# KeyTop.net
KiCad netlist of a schematic drawn in EasyEDA Pro
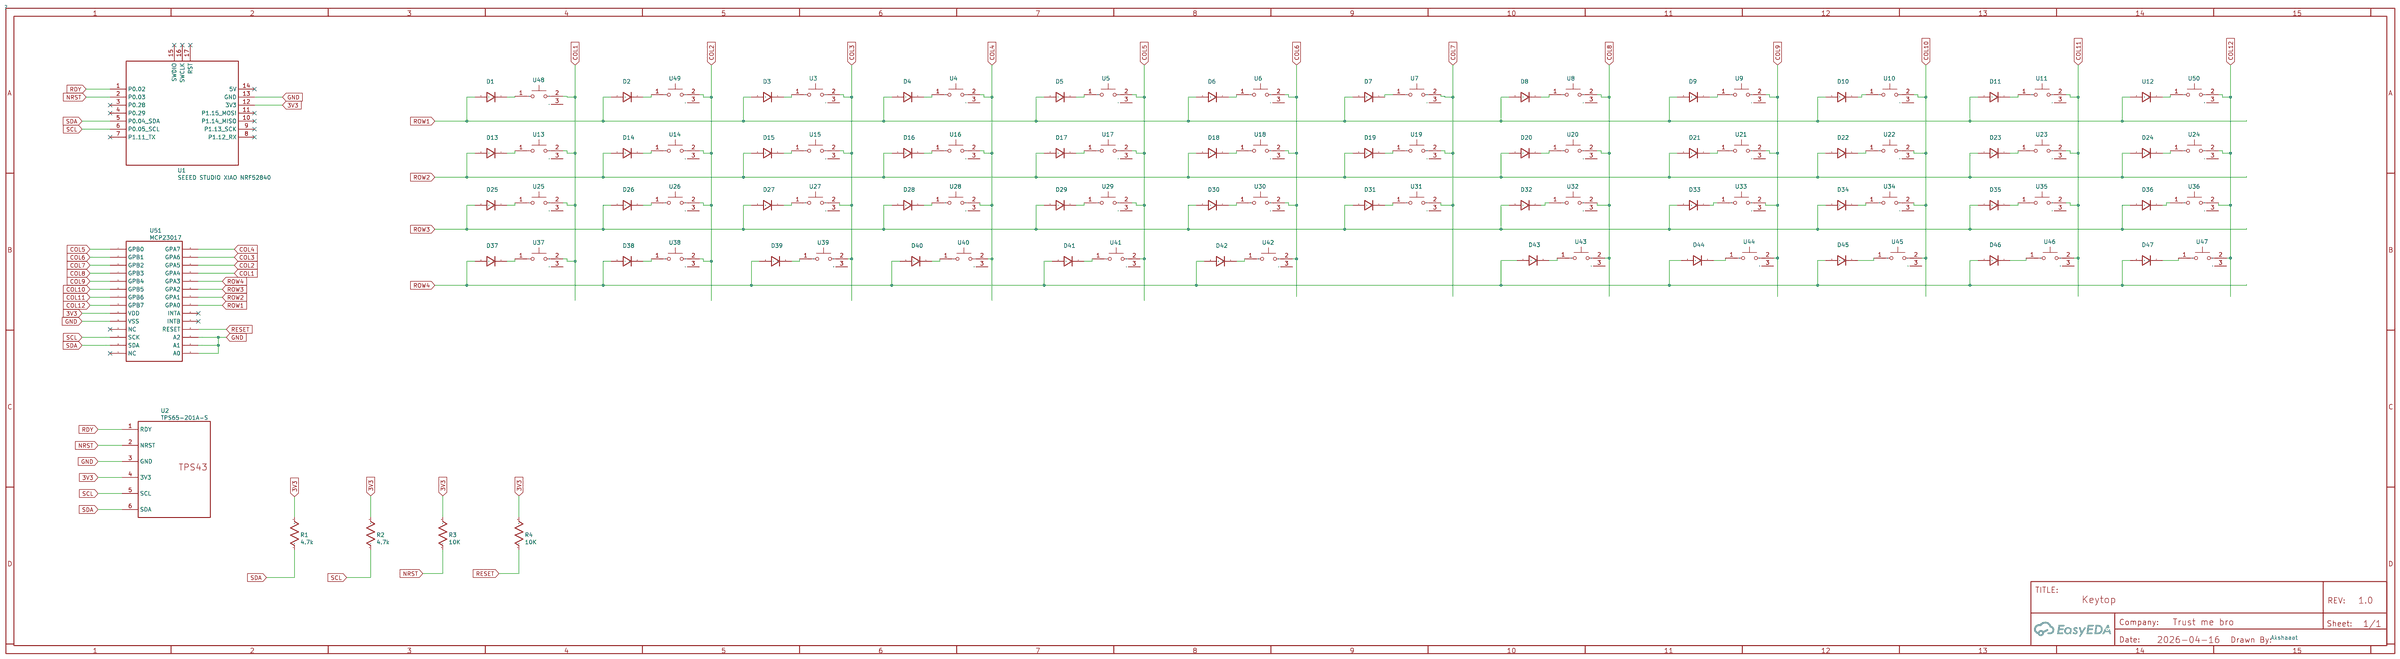
[diagram p0: schematic sheet]

(export (version "E")
  (design (tool "Eeschema 10.0.6"))
  (components
    (comp (ref "D1")
      (value "1N4148")
      (footprint "easyedapro:SOD-123_L2.8-W1.8-LS3.7-RD")
      (fields
        (field (name "Manufacturer Part") "1N4007W")
        (field (name "Manufacturer") "BLUE ROCKET")
        (field (name "Contributor") "LCEDA_Lib")
      )
      (libsource (lib "easyedapro") (part "1N4148"))
    )
    (comp (ref "D2")
      (value "1N4148")
      (footprint "easyedapro:SOD-123_L2.8-W1.8-LS3.7-RD")
      (fields
        (field (name "Manufacturer Part") "1N4007W")
        (field (name "Manufacturer") "BLUE ROCKET")
        (field (name "Contributor") "LCEDA_Lib")
      )
      (libsource (lib "easyedapro") (part "1N4148"))
    )
    (comp (ref "D3")
      (value "1N4148")
      (footprint "easyedapro:SOD-123_L2.8-W1.8-LS3.7-RD")
      (fields
        (field (name "Manufacturer Part") "1N4007W")
        (field (name "Manufacturer") "BLUE ROCKET")
        (field (name "Contributor") "LCEDA_Lib")
      )
      (libsource (lib "easyedapro") (part "1N4148"))
    )
    (comp (ref "D4")
      (value "1N4148")
      (footprint "easyedapro:SOD-123_L2.8-W1.8-LS3.7-RD")
      (fields
        (field (name "Manufacturer Part") "1N4007W")
        (field (name "Manufacturer") "BLUE ROCKET")
        (field (name "Contributor") "LCEDA_Lib")
      )
      (libsource (lib "easyedapro") (part "1N4148"))
    )
    (comp (ref "D5")
      (value "1N4148")
      (footprint "easyedapro:SOD-123_L2.8-W1.8-LS3.7-RD")
      (fields
        (field (name "Manufacturer Part") "1N4007W")
        (field (name "Manufacturer") "BLUE ROCKET")
        (field (name "Contributor") "LCEDA_Lib")
      )
      (libsource (lib "easyedapro") (part "1N4148"))
    )
    (comp (ref "D6")
      (value "1N4148")
      (footprint "easyedapro:SOD-123_L2.8-W1.8-LS3.7-RD")
      (fields
        (field (name "Manufacturer Part") "1N4007W")
        (field (name "Manufacturer") "BLUE ROCKET")
        (field (name "Contributor") "LCEDA_Lib")
      )
      (libsource (lib "easyedapro") (part "1N4148"))
    )
    (comp (ref "D7")
      (value "1N4148")
      (footprint "easyedapro:SOD-123_L2.8-W1.8-LS3.7-RD")
      (fields
        (field (name "Manufacturer Part") "1N4007W")
        (field (name "Manufacturer") "BLUE ROCKET")
        (field (name "Contributor") "LCEDA_Lib")
      )
      (libsource (lib "easyedapro") (part "1N4148"))
    )
    (comp (ref "D8")
      (value "1N4148")
      (footprint "easyedapro:SOD-123_L2.8-W1.8-LS3.7-RD")
      (fields
        (field (name "Manufacturer Part") "1N4007W")
        (field (name "Manufacturer") "BLUE ROCKET")
        (field (name "Contributor") "LCEDA_Lib")
      )
      (libsource (lib "easyedapro") (part "1N4148"))
    )
    (comp (ref "D9")
      (value "1N4148")
      (footprint "easyedapro:SOD-123_L2.8-W1.8-LS3.7-RD")
      (fields
        (field (name "Manufacturer Part") "1N4007W")
        (field (name "Manufacturer") "BLUE ROCKET")
        (field (name "Contributor") "LCEDA_Lib")
      )
      (libsource (lib "easyedapro") (part "1N4148"))
    )
    (comp (ref "D10")
      (value "1N4148")
      (footprint "easyedapro:SOD-123_L2.8-W1.8-LS3.7-RD")
      (fields
        (field (name "Manufacturer Part") "1N4007W")
        (field (name "Manufacturer") "BLUE ROCKET")
        (field (name "Contributor") "LCEDA_Lib")
      )
      (libsource (lib "easyedapro") (part "1N4148"))
    )
    (comp (ref "D11")
      (value "1N4148")
      (footprint "easyedapro:SOD-123_L2.8-W1.8-LS3.7-RD")
      (fields
        (field (name "Manufacturer Part") "1N4007W")
        (field (name "Manufacturer") "BLUE ROCKET")
        (field (name "Contributor") "LCEDA_Lib")
      )
      (libsource (lib "easyedapro") (part "1N4148"))
    )
    (comp (ref "D13")
      (value "1N4148")
      (footprint "easyedapro:SOD-123_L2.8-W1.8-LS3.7-RD")
      (fields
        (field (name "Manufacturer Part") "1N4007W")
        (field (name "Manufacturer") "BLUE ROCKET")
        (field (name "Contributor") "LCEDA_Lib")
      )
      (libsource (lib "easyedapro") (part "1N4148"))
    )
    (comp (ref "D14")
      (value "1N4148")
      (footprint "easyedapro:SOD-123_L2.8-W1.8-LS3.7-RD")
      (fields
        (field (name "Manufacturer Part") "1N4007W")
        (field (name "Manufacturer") "BLUE ROCKET")
        (field (name "Contributor") "LCEDA_Lib")
      )
      (libsource (lib "easyedapro") (part "1N4148"))
    )
    (comp (ref "D15")
      (value "1N4148")
      (footprint "easyedapro:SOD-123_L2.8-W1.8-LS3.7-RD")
      (fields
        (field (name "Manufacturer Part") "1N4007W")
        (field (name "Manufacturer") "BLUE ROCKET")
        (field (name "Contributor") "LCEDA_Lib")
      )
      (libsource (lib "easyedapro") (part "1N4148"))
    )
    (comp (ref "D16")
      (value "1N4148")
      (footprint "easyedapro:SOD-123_L2.8-W1.8-LS3.7-RD")
      (fields
        (field (name "Manufacturer Part") "1N4007W")
        (field (name "Manufacturer") "BLUE ROCKET")
        (field (name "Contributor") "LCEDA_Lib")
      )
      (libsource (lib "easyedapro") (part "1N4148"))
    )
    (comp (ref "D17")
      (value "1N4148")
      (footprint "easyedapro:SOD-123_L2.8-W1.8-LS3.7-RD")
      (fields
        (field (name "Manufacturer Part") "1N4007W")
        (field (name "Manufacturer") "BLUE ROCKET")
        (field (name "Contributor") "LCEDA_Lib")
      )
      (libsource (lib "easyedapro") (part "1N4148"))
    )
    (comp (ref "D18")
      (value "1N4148")
      (footprint "easyedapro:SOD-123_L2.8-W1.8-LS3.7-RD")
      (fields
        (field (name "Manufacturer Part") "1N4007W")
        (field (name "Manufacturer") "BLUE ROCKET")
        (field (name "Contributor") "LCEDA_Lib")
      )
      (libsource (lib "easyedapro") (part "1N4148"))
    )
    (comp (ref "D19")
      (value "1N4148")
      (footprint "easyedapro:SOD-123_L2.8-W1.8-LS3.7-RD")
      (fields
        (field (name "Manufacturer Part") "1N4007W")
        (field (name "Manufacturer") "BLUE ROCKET")
        (field (name "Contributor") "LCEDA_Lib")
      )
      (libsource (lib "easyedapro") (part "1N4148"))
    )
    (comp (ref "D20")
      (value "1N4148")
      (footprint "easyedapro:SOD-123_L2.8-W1.8-LS3.7-RD")
      (fields
        (field (name "Manufacturer Part") "1N4007W")
        (field (name "Manufacturer") "BLUE ROCKET")
        (field (name "Contributor") "LCEDA_Lib")
      )
      (libsource (lib "easyedapro") (part "1N4148"))
    )
    (comp (ref "D21")
      (value "1N4148")
      (footprint "easyedapro:SOD-123_L2.8-W1.8-LS3.7-RD")
      (fields
        (field (name "Manufacturer Part") "1N4007W")
        (field (name "Manufacturer") "BLUE ROCKET")
        (field (name "Contributor") "LCEDA_Lib")
      )
      (libsource (lib "easyedapro") (part "1N4148"))
    )
    (comp (ref "D22")
      (value "1N4148")
      (footprint "easyedapro:SOD-123_L2.8-W1.8-LS3.7-RD")
      (fields
        (field (name "Manufacturer Part") "1N4007W")
        (field (name "Manufacturer") "BLUE ROCKET")
        (field (name "Contributor") "LCEDA_Lib")
      )
      (libsource (lib "easyedapro") (part "1N4148"))
    )
    (comp (ref "D23")
      (value "1N4148")
      (footprint "easyedapro:SOD-123_L2.8-W1.8-LS3.7-RD")
      (fields
        (field (name "Manufacturer Part") "1N4007W")
        (field (name "Manufacturer") "BLUE ROCKET")
        (field (name "Contributor") "LCEDA_Lib")
      )
      (libsource (lib "easyedapro") (part "1N4148"))
    )
    (comp (ref "D24")
      (value "1N4148")
      (footprint "easyedapro:SOD-123_L2.8-W1.8-LS3.7-RD")
      (fields
        (field (name "Manufacturer Part") "1N4007W")
        (field (name "Manufacturer") "BLUE ROCKET")
        (field (name "Contributor") "LCEDA_Lib")
      )
      (libsource (lib "easyedapro") (part "1N4148"))
    )
    (comp (ref "D25")
      (value "1N4148")
      (footprint "easyedapro:SOD-123_L2.8-W1.8-LS3.7-RD")
      (fields
        (field (name "Manufacturer Part") "1N4007W")
        (field (name "Manufacturer") "BLUE ROCKET")
        (field (name "Contributor") "LCEDA_Lib")
      )
      (libsource (lib "easyedapro") (part "1N4148"))
    )
    (comp (ref "D26")
      (value "1N4148")
      (footprint "easyedapro:SOD-123_L2.8-W1.8-LS3.7-RD")
      (fields
        (field (name "Manufacturer Part") "1N4007W")
        (field (name "Manufacturer") "BLUE ROCKET")
        (field (name "Contributor") "LCEDA_Lib")
      )
      (libsource (lib "easyedapro") (part "1N4148"))
    )
    (comp (ref "D27")
      (value "1N4148")
      (footprint "easyedapro:SOD-123_L2.8-W1.8-LS3.7-RD")
      (fields
        (field (name "Manufacturer Part") "1N4007W")
        (field (name "Manufacturer") "BLUE ROCKET")
        (field (name "Contributor") "LCEDA_Lib")
      )
      (libsource (lib "easyedapro") (part "1N4148"))
    )
    (comp (ref "D28")
      (value "1N4148")
      (footprint "easyedapro:SOD-123_L2.8-W1.8-LS3.7-RD")
      (fields
        (field (name "Manufacturer Part") "1N4007W")
        (field (name "Manufacturer") "BLUE ROCKET")
        (field (name "Contributor") "LCEDA_Lib")
      )
      (libsource (lib "easyedapro") (part "1N4148"))
    )
    (comp (ref "D29")
      (value "1N4148")
      (footprint "easyedapro:SOD-123_L2.8-W1.8-LS3.7-RD")
      (fields
        (field (name "Manufacturer Part") "1N4007W")
        (field (name "Manufacturer") "BLUE ROCKET")
        (field (name "Contributor") "LCEDA_Lib")
      )
      (libsource (lib "easyedapro") (part "1N4148"))
    )
    (comp (ref "D30")
      (value "1N4148")
      (footprint "easyedapro:SOD-123_L2.8-W1.8-LS3.7-RD")
      (fields
        (field (name "Manufacturer Part") "1N4007W")
        (field (name "Manufacturer") "BLUE ROCKET")
        (field (name "Contributor") "LCEDA_Lib")
      )
      (libsource (lib "easyedapro") (part "1N4148"))
    )
    (comp (ref "D31")
      (value "1N4148")
      (footprint "easyedapro:SOD-123_L2.8-W1.8-LS3.7-RD")
      (fields
        (field (name "Manufacturer Part") "1N4007W")
        (field (name "Manufacturer") "BLUE ROCKET")
        (field (name "Contributor") "LCEDA_Lib")
      )
      (libsource (lib "easyedapro") (part "1N4148"))
    )
    (comp (ref "D32")
      (value "1N4148")
      (footprint "easyedapro:SOD-123_L2.8-W1.8-LS3.7-RD")
      (fields
        (field (name "Manufacturer Part") "1N4007W")
        (field (name "Manufacturer") "BLUE ROCKET")
        (field (name "Contributor") "LCEDA_Lib")
      )
      (libsource (lib "easyedapro") (part "1N4148"))
    )
    (comp (ref "D33")
      (value "1N4148")
      (footprint "easyedapro:SOD-123_L2.8-W1.8-LS3.7-RD")
      (fields
        (field (name "Manufacturer Part") "1N4007W")
        (field (name "Manufacturer") "BLUE ROCKET")
        (field (name "Contributor") "LCEDA_Lib")
      )
      (libsource (lib "easyedapro") (part "1N4148"))
    )
    (comp (ref "D34")
      (value "1N4148")
      (footprint "easyedapro:SOD-123_L2.8-W1.8-LS3.7-RD")
      (fields
        (field (name "Manufacturer Part") "1N4007W")
        (field (name "Manufacturer") "BLUE ROCKET")
        (field (name "Contributor") "LCEDA_Lib")
      )
      (libsource (lib "easyedapro") (part "1N4148"))
    )
    (comp (ref "D35")
      (value "1N4148")
      (footprint "easyedapro:SOD-123_L2.8-W1.8-LS3.7-RD")
      (fields
        (field (name "Manufacturer Part") "1N4007W")
        (field (name "Manufacturer") "BLUE ROCKET")
        (field (name "Contributor") "LCEDA_Lib")
      )
      (libsource (lib "easyedapro") (part "1N4148"))
    )
    (comp (ref "D36")
      (value "1N4148")
      (footprint "easyedapro:SOD-123_L2.8-W1.8-LS3.7-RD")
      (fields
        (field (name "Manufacturer Part") "1N4007W")
        (field (name "Manufacturer") "BLUE ROCKET")
        (field (name "Contributor") "LCEDA_Lib")
      )
      (libsource (lib "easyedapro") (part "1N4148"))
    )
    (comp (ref "D37")
      (value "1N4148")
      (footprint "easyedapro:SOD-123_L2.8-W1.8-LS3.7-RD")
      (fields
        (field (name "Manufacturer Part") "1N4007W")
        (field (name "Manufacturer") "BLUE ROCKET")
        (field (name "Contributor") "LCEDA_Lib")
      )
      (libsource (lib "easyedapro") (part "1N4148"))
    )
    (comp (ref "D38")
      (value "1N4148")
      (footprint "easyedapro:SOD-123_L2.8-W1.8-LS3.7-RD")
      (fields
        (field (name "Manufacturer Part") "1N4007W")
        (field (name "Manufacturer") "BLUE ROCKET")
        (field (name "Contributor") "LCEDA_Lib")
      )
      (libsource (lib "easyedapro") (part "1N4148"))
    )
    (comp (ref "D39")
      (value "1N4148")
      (footprint "easyedapro:SOD-123_L2.8-W1.8-LS3.7-RD")
      (fields
        (field (name "Manufacturer Part") "1N4007W")
        (field (name "Manufacturer") "BLUE ROCKET")
        (field (name "Contributor") "LCEDA_Lib")
      )
      (libsource (lib "easyedapro") (part "1N4148"))
    )
    (comp (ref "D40")
      (value "1N4148")
      (footprint "easyedapro:SOD-123_L2.8-W1.8-LS3.7-RD")
      (fields
        (field (name "Manufacturer Part") "1N4007W")
        (field (name "Manufacturer") "BLUE ROCKET")
        (field (name "Contributor") "LCEDA_Lib")
      )
      (libsource (lib "easyedapro") (part "1N4148"))
    )
    (comp (ref "D41")
      (value "1N4148")
      (footprint "easyedapro:SOD-123_L2.8-W1.8-LS3.7-RD")
      (fields
        (field (name "Manufacturer Part") "1N4007W")
        (field (name "Manufacturer") "BLUE ROCKET")
        (field (name "Contributor") "LCEDA_Lib")
      )
      (libsource (lib "easyedapro") (part "1N4148"))
    )
    (comp (ref "D42")
      (value "1N4148")
      (footprint "easyedapro:SOD-123_L2.8-W1.8-LS3.7-RD")
      (fields
        (field (name "Manufacturer Part") "1N4007W")
        (field (name "Manufacturer") "BLUE ROCKET")
        (field (name "Contributor") "LCEDA_Lib")
      )
      (libsource (lib "easyedapro") (part "1N4148"))
    )
    (comp (ref "D43")
      (value "1N4148")
      (footprint "easyedapro:SOD-123_L2.8-W1.8-LS3.7-RD")
      (fields
        (field (name "Manufacturer Part") "1N4007W")
        (field (name "Manufacturer") "BLUE ROCKET")
        (field (name "Contributor") "LCEDA_Lib")
      )
      (libsource (lib "easyedapro") (part "1N4148"))
    )
    (comp (ref "D44")
      (value "1N4148")
      (footprint "easyedapro:SOD-123_L2.8-W1.8-LS3.7-RD")
      (fields
        (field (name "Manufacturer Part") "1N4007W")
        (field (name "Manufacturer") "BLUE ROCKET")
        (field (name "Contributor") "LCEDA_Lib")
      )
      (libsource (lib "easyedapro") (part "1N4148"))
    )
    (comp (ref "D45")
      (value "1N4148")
      (footprint "easyedapro:SOD-123_L2.8-W1.8-LS3.7-RD")
      (fields
        (field (name "Manufacturer Part") "1N4007W")
        (field (name "Manufacturer") "BLUE ROCKET")
        (field (name "Contributor") "LCEDA_Lib")
      )
      (libsource (lib "easyedapro") (part "1N4148"))
    )
    (comp (ref "D46")
      (value "1N4148")
      (footprint "easyedapro:SOD-123_L2.8-W1.8-LS3.7-RD")
      (fields
        (field (name "Manufacturer Part") "1N4007W")
        (field (name "Manufacturer") "BLUE ROCKET")
        (field (name "Contributor") "LCEDA_Lib")
      )
      (libsource (lib "easyedapro") (part "1N4148"))
    )
    (comp (ref "D47")
      (value "1N4148")
      (footprint "easyedapro:SOD-123_L2.8-W1.8-LS3.7-RD")
      (fields
        (field (name "Manufacturer Part") "1N4007W")
        (field (name "Manufacturer") "BLUE ROCKET")
        (field (name "Contributor") "LCEDA_Lib")
      )
      (libsource (lib "easyedapro") (part "1N4148"))
    )
    (comp (ref "R1")
      (value "4.7k")
      (footprint "easyedapro:R0603")
      (fields (field (name "Contributor") "LCEDA_Lib"))
      (libsource (lib "easyedapro") (part "4.7k"))
    )
    (comp (ref "R2")
      (value "4.7k")
      (footprint "easyedapro:R0603")
      (fields (field (name "Contributor") "LCEDA_Lib"))
      (libsource (lib "easyedapro") (part "4.7k"))
    )
    (comp (ref "R3")
      (value "10K")
      (footprint "easyedapro:R0603")
      (fields (field (name "Contributor") "LCEDA_Lib"))
      (libsource (lib "easyedapro") (part "10K"))
    )
    (comp (ref "R4")
      (value "10K")
      (footprint "easyedapro:R0603")
      (fields (field (name "Contributor") "LCEDA_Lib"))
      (libsource (lib "easyedapro") (part "10K"))
    )
    (comp (ref "U1")
      (value "SEEED STUDIO XIAO NRF52840")
      (footprint "easyedapro:SEEED STUDIO XIAO NRF52840")
      (fields (field (name "Contributor") "hafeneger"))
      (libsource (lib "easyedapro") (part "SEEED STUDIO XIAO NRF52840"))
    )
    (comp (ref "U2")
      (value "TPS65-201A-S")
      (footprint "easyedapro:TPS65-201A-S")
      (fields (field (name "Manufacturer") "Azoteq") (field (name "Contributor") "ilysnwflk"))
      (libsource (lib "easyedapro") (part "TPS65-201A-S"))
    )
    (comp (ref "U3")
      (value "CPG135301D02")
      (footprint "easyedapro:KEY-TH_CPG135301D02")
      (fields (field (name "Manufacturer") "Kailh(凯华)"))
      (libsource (lib "easyedapro") (part "CPG135301D02"))
    )
    (comp (ref "U4")
      (value "CPG135301D02")
      (footprint "easyedapro:KEY-TH_CPG135301D02")
      (fields (field (name "Manufacturer") "Kailh(凯华)"))
      (libsource (lib "easyedapro") (part "CPG135301D02"))
    )
    (comp (ref "U5")
      (value "CPG135301D02")
      (footprint "easyedapro:KEY-TH_CPG135301D02")
      (fields (field (name "Manufacturer") "Kailh(凯华)"))
      (libsource (lib "easyedapro") (part "CPG135301D02"))
    )
    (comp (ref "U6")
      (value "CPG135301D02")
      (footprint "easyedapro:KEY-TH_CPG135301D02")
      (fields (field (name "Manufacturer") "Kailh(凯华)"))
      (libsource (lib "easyedapro") (part "CPG135301D02"))
    )
    (comp (ref "U7")
      (value "CPG135301D02")
      (footprint "easyedapro:KEY-TH_CPG135301D02")
      (fields (field (name "Manufacturer") "Kailh(凯华)"))
      (libsource (lib "easyedapro") (part "CPG135301D02"))
    )
    (comp (ref "U8")
      (value "CPG135301D02")
      (footprint "easyedapro:KEY-TH_CPG135301D02")
      (fields (field (name "Manufacturer") "Kailh(凯华)"))
      (libsource (lib "easyedapro") (part "CPG135301D02"))
    )
    (comp (ref "U9")
      (value "CPG135301D02")
      (footprint "easyedapro:KEY-TH_CPG135301D02")
      (fields (field (name "Manufacturer") "Kailh(凯华)"))
      (libsource (lib "easyedapro") (part "CPG135301D02"))
    )
    (comp (ref "U10")
      (value "CPG135301D02")
      (footprint "easyedapro:KEY-TH_CPG135301D02")
      (fields (field (name "Manufacturer") "Kailh(凯华)"))
      (libsource (lib "easyedapro") (part "CPG135301D02"))
    )
    (comp (ref "U11")
      (value "CPG135301D02")
      (footprint "easyedapro:KEY-TH_CPG135301D02")
      (fields (field (name "Manufacturer") "Kailh(凯华)"))
      (libsource (lib "easyedapro") (part "CPG135301D02"))
    )
    (comp (ref "U12")
      (value "1N4148")
      (footprint "easyedapro:SOD-123_L2.8-W1.8-LS3.7-RD")
      (fields
        (field (name "Manufacturer Part") "1N4007W")
        (field (name "Manufacturer") "BLUE ROCKET")
        (field (name "Contributor") "LCEDA_Lib")
      )
      (libsource (lib "easyedapro") (part "1N4148"))
    )
    (comp (ref "U13")
      (value "CPG135301D02")
      (footprint "easyedapro:KEY-TH_CPG135301D02")
      (fields (field (name "Manufacturer") "Kailh(凯华)"))
      (libsource (lib "easyedapro") (part "CPG135301D02"))
    )
    (comp (ref "U14")
      (value "CPG135301D02")
      (footprint "easyedapro:KEY-TH_CPG135301D02")
      (fields (field (name "Manufacturer") "Kailh(凯华)"))
      (libsource (lib "easyedapro") (part "CPG135301D02"))
    )
    (comp (ref "U15")
      (value "CPG135301D02")
      (footprint "easyedapro:KEY-TH_CPG135301D02")
      (fields (field (name "Manufacturer") "Kailh(凯华)"))
      (libsource (lib "easyedapro") (part "CPG135301D02"))
    )
    (comp (ref "U16")
      (value "CPG135301D02")
      (footprint "easyedapro:KEY-TH_CPG135301D02")
      (fields (field (name "Manufacturer") "Kailh(凯华)"))
      (libsource (lib "easyedapro") (part "CPG135301D02"))
    )
    (comp (ref "U17")
      (value "CPG135301D02")
      (footprint "easyedapro:KEY-TH_CPG135301D02")
      (fields (field (name "Manufacturer") "Kailh(凯华)"))
      (libsource (lib "easyedapro") (part "CPG135301D02"))
    )
    (comp (ref "U18")
      (value "CPG135301D02")
      (footprint "easyedapro:KEY-TH_CPG135301D02")
      (fields (field (name "Manufacturer") "Kailh(凯华)"))
      (libsource (lib "easyedapro") (part "CPG135301D02"))
    )
    (comp (ref "U19")
      (value "CPG135301D02")
      (footprint "easyedapro:KEY-TH_CPG135301D02")
      (fields (field (name "Manufacturer") "Kailh(凯华)"))
      (libsource (lib "easyedapro") (part "CPG135301D02"))
    )
    (comp (ref "U20")
      (value "CPG135301D02")
      (footprint "easyedapro:KEY-TH_CPG135301D02")
      (fields (field (name "Manufacturer") "Kailh(凯华)"))
      (libsource (lib "easyedapro") (part "CPG135301D02"))
    )
    (comp (ref "U21")
      (value "CPG135301D02")
      (footprint "easyedapro:KEY-TH_CPG135301D02")
      (fields (field (name "Manufacturer") "Kailh(凯华)"))
      (libsource (lib "easyedapro") (part "CPG135301D02"))
    )
    (comp (ref "U22")
      (value "CPG135301D02")
      (footprint "easyedapro:KEY-TH_CPG135301D02")
      (fields (field (name "Manufacturer") "Kailh(凯华)"))
      (libsource (lib "easyedapro") (part "CPG135301D02"))
    )
    (comp (ref "U23")
      (value "CPG135301D02")
      (footprint "easyedapro:KEY-TH_CPG135301D02")
      (fields (field (name "Manufacturer") "Kailh(凯华)"))
      (libsource (lib "easyedapro") (part "CPG135301D02"))
    )
    (comp (ref "U24")
      (value "CPG135301D02")
      (footprint "easyedapro:KEY-TH_CPG135301D02")
      (fields (field (name "Manufacturer") "Kailh(凯华)"))
      (libsource (lib "easyedapro") (part "CPG135301D02"))
    )
    (comp (ref "U25")
      (value "CPG135301D02")
      (footprint "easyedapro:KEY-TH_CPG135301D02")
      (fields (field (name "Manufacturer") "Kailh(凯华)"))
      (libsource (lib "easyedapro") (part "CPG135301D02"))
    )
    (comp (ref "U26")
      (value "CPG135301D02")
      (footprint "easyedapro:KEY-TH_CPG135301D02")
      (fields (field (name "Manufacturer") "Kailh(凯华)"))
      (libsource (lib "easyedapro") (part "CPG135301D02"))
    )
    (comp (ref "U27")
      (value "CPG135301D02")
      (footprint "easyedapro:KEY-TH_CPG135301D02")
      (fields (field (name "Manufacturer") "Kailh(凯华)"))
      (libsource (lib "easyedapro") (part "CPG135301D02"))
    )
    (comp (ref "U28")
      (value "CPG135301D02")
      (footprint "easyedapro:KEY-TH_CPG135301D02")
      (fields (field (name "Manufacturer") "Kailh(凯华)"))
      (libsource (lib "easyedapro") (part "CPG135301D02"))
    )
    (comp (ref "U29")
      (value "CPG135301D02")
      (footprint "easyedapro:KEY-TH_CPG135301D02")
      (fields (field (name "Manufacturer") "Kailh(凯华)"))
      (libsource (lib "easyedapro") (part "CPG135301D02"))
    )
    (comp (ref "U30")
      (value "CPG135301D02")
      (footprint "easyedapro:KEY-TH_CPG135301D02")
      (fields (field (name "Manufacturer") "Kailh(凯华)"))
      (libsource (lib "easyedapro") (part "CPG135301D02"))
    )
    (comp (ref "U31")
      (value "CPG135301D02")
      (footprint "easyedapro:KEY-TH_CPG135301D02")
      (fields (field (name "Manufacturer") "Kailh(凯华)"))
      (libsource (lib "easyedapro") (part "CPG135301D02"))
    )
    (comp (ref "U32")
      (value "CPG135301D02")
      (footprint "easyedapro:KEY-TH_CPG135301D02")
      (fields (field (name "Manufacturer") "Kailh(凯华)"))
      (libsource (lib "easyedapro") (part "CPG135301D02"))
    )
    (comp (ref "U33")
      (value "CPG135301D02")
      (footprint "easyedapro:KEY-TH_CPG135301D02")
      (fields (field (name "Manufacturer") "Kailh(凯华)"))
      (libsource (lib "easyedapro") (part "CPG135301D02"))
    )
    (comp (ref "U34")
      (value "CPG135301D02")
      (footprint "easyedapro:KEY-TH_CPG135301D02")
      (fields (field (name "Manufacturer") "Kailh(凯华)"))
      (libsource (lib "easyedapro") (part "CPG135301D02"))
    )
    (comp (ref "U35")
      (value "CPG135301D02")
      (footprint "easyedapro:KEY-TH_CPG135301D02")
      (fields (field (name "Manufacturer") "Kailh(凯华)"))
      (libsource (lib "easyedapro") (part "CPG135301D02"))
    )
    (comp (ref "U36")
      (value "CPG135301D02")
      (footprint "easyedapro:KEY-TH_CPG135301D02")
      (fields (field (name "Manufacturer") "Kailh(凯华)"))
      (libsource (lib "easyedapro") (part "CPG135301D02"))
    )
    (comp (ref "U37")
      (value "CPG135301D02")
      (footprint "easyedapro:KEY-TH_CPG135301D02")
      (fields (field (name "Manufacturer") "Kailh(凯华)"))
      (libsource (lib "easyedapro") (part "CPG135301D02"))
    )
    (comp (ref "U38")
      (value "CPG135301D02")
      (footprint "easyedapro:KEY-TH_CPG135301D02")
      (fields (field (name "Manufacturer") "Kailh(凯华)"))
      (libsource (lib "easyedapro") (part "CPG135301D02"))
    )
    (comp (ref "U39")
      (value "CPG135301D02")
      (footprint "easyedapro:KEY-TH_CPG135301D02")
      (fields (field (name "Manufacturer") "Kailh(凯华)"))
      (libsource (lib "easyedapro") (part "CPG135301D02"))
    )
    (comp (ref "U40")
      (value "CPG135301D02")
      (footprint "easyedapro:KEY-TH_CPG135301D02")
      (fields (field (name "Manufacturer") "Kailh(凯华)"))
      (libsource (lib "easyedapro") (part "CPG135301D02"))
    )
    (comp (ref "U41")
      (value "CPG135301D02")
      (footprint "easyedapro:KEY-TH_CPG135301D02")
      (fields (field (name "Manufacturer") "Kailh(凯华)"))
      (libsource (lib "easyedapro") (part "CPG135301D02"))
    )
    (comp (ref "U42")
      (value "CPG135301D02")
      (footprint "easyedapro:KEY-TH_CPG135301D02")
      (fields (field (name "Manufacturer") "Kailh(凯华)"))
      (libsource (lib "easyedapro") (part "CPG135301D02"))
    )
    (comp (ref "U43")
      (value "CPG135301D02")
      (footprint "easyedapro:KEY-TH_CPG135301D02")
      (fields (field (name "Manufacturer") "Kailh(凯华)"))
      (libsource (lib "easyedapro") (part "CPG135301D02"))
    )
    (comp (ref "U44")
      (value "CPG135301D02")
      (footprint "easyedapro:KEY-TH_CPG135301D02")
      (fields (field (name "Manufacturer") "Kailh(凯华)"))
      (libsource (lib "easyedapro") (part "CPG135301D02"))
    )
    (comp (ref "U45")
      (value "CPG135301D02")
      (footprint "easyedapro:KEY-TH_CPG135301D02")
      (fields (field (name "Manufacturer") "Kailh(凯华)"))
      (libsource (lib "easyedapro") (part "CPG135301D02"))
    )
    (comp (ref "U46")
      (value "CPG135301D02")
      (footprint "easyedapro:KEY-TH_CPG135301D02")
      (fields (field (name "Manufacturer") "Kailh(凯华)"))
      (libsource (lib "easyedapro") (part "CPG135301D02"))
    )
    (comp (ref "U47")
      (value "CPG135301D02")
      (footprint "easyedapro:KEY-TH_CPG135301D02")
      (fields (field (name "Manufacturer") "Kailh(凯华)"))
      (libsource (lib "easyedapro") (part "CPG135301D02"))
    )
    (comp (ref "U48")
      (value "CPG135301D02")
      (footprint "easyedapro:KEY-TH_CPG135301D02")
      (fields (field (name "Manufacturer") "Kailh(凯华)"))
      (libsource (lib "easyedapro") (part "CPG135301D02"))
    )
    (comp (ref "U49")
      (value "CPG135301D02")
      (footprint "easyedapro:KEY-TH_CPG135301D02")
      (fields (field (name "Manufacturer") "Kailh(凯华)"))
      (libsource (lib "easyedapro") (part "CPG135301D02"))
    )
    (comp (ref "U50")
      (value "CPG135301D02")
      (footprint "easyedapro:KEY-TH_CPG135301D02")
      (fields (field (name "Manufacturer") "Kailh(凯华)"))
      (libsource (lib "easyedapro") (part "CPG135301D02"))
    )
    (comp (ref "U51")
      (value "MCP23017")
      (footprint "easyedapro:MCP23017-E/SP")
      (fields (field (name "Contributor") "bartvanhecke"))
      (libsource (lib "easyedapro") (part "MCP23017"))
    )
  )
  (nets
    (net (code "1") (name "3V3") (class "Default")
      (node (ref "R1") (pin "2") (pinfunction "2_2") (pintype "unspecified"))
      (node (ref "R2") (pin "2") (pinfunction "2_2") (pintype "unspecified"))
      (node (ref "R3") (pin "2") (pinfunction "2_2") (pintype "unspecified"))
      (node (ref "R4") (pin "2") (pinfunction "2_2") (pintype "unspecified"))
      (node (ref "U1") (pin "12") (pinfunction "3V3_12") (pintype "unspecified"))
      (node (ref "U2") (pin "4") (pinfunction "3V3_4") (pintype "unspecified"))
      (node (ref "U51") (pin "9") (pinfunction "VDD_9") (pintype "unspecified"))
    )
    (net (code "2") (name "COL1") (class "Default")
      (node (ref "U13") (pin "2") (pinfunction "2_2") (pintype "unspecified"))
      (node (ref "U25") (pin "2") (pinfunction "2_2") (pintype "unspecified"))
      (node (ref "U37") (pin "2") (pinfunction "2_2") (pintype "unspecified"))
      (node (ref "U48") (pin "2") (pinfunction "2_2") (pintype "unspecified"))
      (node (ref "U51") (pin "25") (pinfunction "GPA4_25") (pintype "unspecified"))
    )
    (net (code "3") (name "COL2") (class "Default")
      (node (ref "U14") (pin "2") (pinfunction "2_2") (pintype "unspecified"))
      (node (ref "U26") (pin "2") (pinfunction "2_2") (pintype "unspecified"))
      (node (ref "U38") (pin "2") (pinfunction "2_2") (pintype "unspecified"))
      (node (ref "U49") (pin "2") (pinfunction "2_2") (pintype "unspecified"))
      (node (ref "U51") (pin "26") (pinfunction "GPA5_26") (pintype "unspecified"))
    )
    (net (code "4") (name "COL3") (class "Default")
      (node (ref "U15") (pin "2") (pinfunction "2_2") (pintype "unspecified"))
      (node (ref "U27") (pin "2") (pinfunction "2_2") (pintype "unspecified"))
      (node (ref "U3") (pin "2") (pinfunction "2_2") (pintype "unspecified"))
      (node (ref "U39") (pin "2") (pinfunction "2_2") (pintype "unspecified"))
      (node (ref "U51") (pin "27") (pinfunction "GPA6_27") (pintype "unspecified"))
    )
    (net (code "5") (name "COL4") (class "Default")
      (node (ref "U16") (pin "2") (pinfunction "2_2") (pintype "unspecified"))
      (node (ref "U28") (pin "2") (pinfunction "2_2") (pintype "unspecified"))
      (node (ref "U4") (pin "2") (pinfunction "2_2") (pintype "unspecified"))
      (node (ref "U40") (pin "2") (pinfunction "2_2") (pintype "unspecified"))
      (node (ref "U51") (pin "28") (pinfunction "GPA7_28") (pintype "unspecified"))
    )
    (net (code "6") (name "COL5") (class "Default")
      (node (ref "U17") (pin "2") (pinfunction "2_2") (pintype "unspecified"))
      (node (ref "U29") (pin "2") (pinfunction "2_2") (pintype "unspecified"))
      (node (ref "U41") (pin "2") (pinfunction "2_2") (pintype "unspecified"))
      (node (ref "U5") (pin "2") (pinfunction "2_2") (pintype "unspecified"))
      (node (ref "U51") (pin "1") (pinfunction "GPB0_1") (pintype "unspecified"))
    )
    (net (code "7") (name "COL6") (class "Default")
      (node (ref "U18") (pin "2") (pinfunction "2_2") (pintype "unspecified"))
      (node (ref "U30") (pin "2") (pinfunction "2_2") (pintype "unspecified"))
      (node (ref "U42") (pin "2") (pinfunction "2_2") (pintype "unspecified"))
      (node (ref "U51") (pin "2") (pinfunction "GPB1_2") (pintype "unspecified"))
      (node (ref "U6") (pin "2") (pinfunction "2_2") (pintype "unspecified"))
    )
    (net (code "8") (name "COL7") (class "Default")
      (node (ref "U19") (pin "2") (pinfunction "2_2") (pintype "unspecified"))
      (node (ref "U31") (pin "2") (pinfunction "2_2") (pintype "unspecified"))
      (node (ref "U51") (pin "3") (pinfunction "GPB2_3") (pintype "unspecified"))
      (node (ref "U7") (pin "2") (pinfunction "2_2") (pintype "unspecified"))
    )
    (net (code "9") (name "COL8") (class "Default")
      (node (ref "U20") (pin "2") (pinfunction "2_2") (pintype "unspecified"))
      (node (ref "U32") (pin "2") (pinfunction "2_2") (pintype "unspecified"))
      (node (ref "U43") (pin "2") (pinfunction "2_2") (pintype "unspecified"))
      (node (ref "U51") (pin "4") (pinfunction "GPB3_4") (pintype "unspecified"))
      (node (ref "U8") (pin "2") (pinfunction "2_2") (pintype "unspecified"))
    )
    (net (code "10") (name "COL9") (class "Default")
      (node (ref "U21") (pin "2") (pinfunction "2_2") (pintype "unspecified"))
      (node (ref "U33") (pin "2") (pinfunction "2_2") (pintype "unspecified"))
      (node (ref "U44") (pin "2") (pinfunction "2_2") (pintype "unspecified"))
      (node (ref "U51") (pin "5") (pinfunction "GPB4_5") (pintype "unspecified"))
      (node (ref "U9") (pin "2") (pinfunction "2_2") (pintype "unspecified"))
    )
    (net (code "11") (name "COL10") (class "Default")
      (node (ref "U10") (pin "2") (pinfunction "2_2") (pintype "unspecified"))
      (node (ref "U22") (pin "2") (pinfunction "2_2") (pintype "unspecified"))
      (node (ref "U34") (pin "2") (pinfunction "2_2") (pintype "unspecified"))
      (node (ref "U45") (pin "2") (pinfunction "2_2") (pintype "unspecified"))
      (node (ref "U51") (pin "6") (pinfunction "GPB5_6") (pintype "unspecified"))
    )
    (net (code "12") (name "COL11") (class "Default")
      (node (ref "U11") (pin "2") (pinfunction "2_2") (pintype "unspecified"))
      (node (ref "U23") (pin "2") (pinfunction "2_2") (pintype "unspecified"))
      (node (ref "U35") (pin "2") (pinfunction "2_2") (pintype "unspecified"))
      (node (ref "U46") (pin "2") (pinfunction "2_2") (pintype "unspecified"))
      (node (ref "U51") (pin "7") (pinfunction "GPB6_7") (pintype "unspecified"))
    )
    (net (code "13") (name "COL12") (class "Default")
      (node (ref "U24") (pin "2") (pinfunction "2_2") (pintype "unspecified"))
      (node (ref "U36") (pin "2") (pinfunction "2_2") (pintype "unspecified"))
      (node (ref "U47") (pin "2") (pinfunction "2_2") (pintype "unspecified"))
      (node (ref "U50") (pin "2") (pinfunction "2_2") (pintype "unspecified"))
      (node (ref "U51") (pin "8") (pinfunction "GPB7_8") (pintype "unspecified"))
    )
    (net (code "14") (name "GND") (class "Default")
      (node (ref "U1") (pin "13") (pinfunction "GND_13") (pintype "unspecified"))
      (node (ref "U2") (pin "3") (pinfunction "GND_3") (pintype "unspecified"))
      (node (ref "U51") (pin "10") (pinfunction "VSS_10") (pintype "unspecified"))
      (node (ref "U51") (pin "15") (pinfunction "A0_15") (pintype "unspecified"))
      (node (ref "U51") (pin "16") (pinfunction "A1_16") (pintype "unspecified"))
      (node (ref "U51") (pin "17") (pinfunction "A2_17") (pintype "unspecified"))
    )
    (net (code "15") (name "NRST") (class "Default")
      (node (ref "R3") (pin "1") (pinfunction "1_1") (pintype "unspecified"))
      (node (ref "U1") (pin "2") (pinfunction "P0.03_2") (pintype "output"))
      (node (ref "U2") (pin "2") (pinfunction "NRST_2") (pintype "unspecified"))
    )
    (net (code "16") (name "Net-(D1-Pad1)") (class "Default")
      (node (ref "D1") (pin "1") (pinfunction "1_1") (pintype "unspecified"))
      (node (ref "U48") (pin "1") (pinfunction "1_1") (pintype "unspecified"))
    )
    (net (code "17") (name "Net-(D2-Pad1)") (class "Default")
      (node (ref "D2") (pin "1") (pinfunction "1_1") (pintype "unspecified"))
      (node (ref "U49") (pin "1") (pinfunction "1_1") (pintype "unspecified"))
    )
    (net (code "18") (name "Net-(D3-Pad1)") (class "Default")
      (node (ref "D3") (pin "1") (pinfunction "1_1") (pintype "unspecified"))
      (node (ref "U3") (pin "1") (pinfunction "1_1") (pintype "unspecified"))
    )
    (net (code "19") (name "Net-(D4-Pad1)") (class "Default")
      (node (ref "D4") (pin "1") (pinfunction "1_1") (pintype "unspecified"))
      (node (ref "U4") (pin "1") (pinfunction "1_1") (pintype "unspecified"))
    )
    (net (code "20") (name "Net-(D5-Pad1)") (class "Default")
      (node (ref "D5") (pin "1") (pinfunction "1_1") (pintype "unspecified"))
      (node (ref "U5") (pin "1") (pinfunction "1_1") (pintype "unspecified"))
    )
    (net (code "21") (name "Net-(D6-Pad1)") (class "Default")
      (node (ref "D6") (pin "1") (pinfunction "1_1") (pintype "unspecified"))
      (node (ref "U6") (pin "1") (pinfunction "1_1") (pintype "unspecified"))
    )
    (net (code "22") (name "Net-(D7-Pad1)") (class "Default")
      (node (ref "D7") (pin "1") (pinfunction "1_1") (pintype "unspecified"))
      (node (ref "U7") (pin "1") (pinfunction "1_1") (pintype "unspecified"))
    )
    (net (code "23") (name "Net-(D8-Pad1)") (class "Default")
      (node (ref "D8") (pin "1") (pinfunction "1_1") (pintype "unspecified"))
      (node (ref "U8") (pin "1") (pinfunction "1_1") (pintype "unspecified"))
    )
    (net (code "24") (name "Net-(D9-Pad1)") (class "Default")
      (node (ref "D9") (pin "1") (pinfunction "1_1") (pintype "unspecified"))
      (node (ref "U9") (pin "1") (pinfunction "1_1") (pintype "unspecified"))
    )
    (net (code "25") (name "Net-(D10-Pad1)") (class "Default")
      (node (ref "D10") (pin "1") (pinfunction "1_1") (pintype "unspecified"))
      (node (ref "U10") (pin "1") (pinfunction "1_1") (pintype "unspecified"))
    )
    (net (code "26") (name "Net-(D11-Pad1)") (class "Default")
      (node (ref "D11") (pin "1") (pinfunction "1_1") (pintype "unspecified"))
      (node (ref "U11") (pin "1") (pinfunction "1_1") (pintype "unspecified"))
    )
    (net (code "27") (name "Net-(D13-Pad1)") (class "Default")
      (node (ref "D13") (pin "1") (pinfunction "1_1") (pintype "unspecified"))
      (node (ref "U13") (pin "1") (pinfunction "1_1") (pintype "unspecified"))
    )
    (net (code "28") (name "Net-(D14-Pad1)") (class "Default")
      (node (ref "D14") (pin "1") (pinfunction "1_1") (pintype "unspecified"))
      (node (ref "U14") (pin "1") (pinfunction "1_1") (pintype "unspecified"))
    )
    (net (code "29") (name "Net-(D15-Pad1)") (class "Default")
      (node (ref "D15") (pin "1") (pinfunction "1_1") (pintype "unspecified"))
      (node (ref "U15") (pin "1") (pinfunction "1_1") (pintype "unspecified"))
    )
    (net (code "30") (name "Net-(D16-Pad1)") (class "Default")
      (node (ref "D16") (pin "1") (pinfunction "1_1") (pintype "unspecified"))
      (node (ref "U16") (pin "1") (pinfunction "1_1") (pintype "unspecified"))
    )
    (net (code "31") (name "Net-(D17-Pad1)") (class "Default")
      (node (ref "D17") (pin "1") (pinfunction "1_1") (pintype "unspecified"))
      (node (ref "U17") (pin "1") (pinfunction "1_1") (pintype "unspecified"))
    )
    (net (code "32") (name "Net-(D18-Pad1)") (class "Default")
      (node (ref "D18") (pin "1") (pinfunction "1_1") (pintype "unspecified"))
      (node (ref "U18") (pin "1") (pinfunction "1_1") (pintype "unspecified"))
    )
    (net (code "33") (name "Net-(D19-Pad1)") (class "Default")
      (node (ref "D19") (pin "1") (pinfunction "1_1") (pintype "unspecified"))
      (node (ref "U19") (pin "1") (pinfunction "1_1") (pintype "unspecified"))
    )
    (net (code "34") (name "Net-(D20-Pad1)") (class "Default")
      (node (ref "D20") (pin "1") (pinfunction "1_1") (pintype "unspecified"))
      (node (ref "U20") (pin "1") (pinfunction "1_1") (pintype "unspecified"))
    )
    (net (code "35") (name "Net-(D21-Pad1)") (class "Default")
      (node (ref "D21") (pin "1") (pinfunction "1_1") (pintype "unspecified"))
      (node (ref "U21") (pin "1") (pinfunction "1_1") (pintype "unspecified"))
    )
    (net (code "36") (name "Net-(D22-Pad1)") (class "Default")
      (node (ref "D22") (pin "1") (pinfunction "1_1") (pintype "unspecified"))
      (node (ref "U22") (pin "1") (pinfunction "1_1") (pintype "unspecified"))
    )
    (net (code "37") (name "Net-(D23-Pad1)") (class "Default")
      (node (ref "D23") (pin "1") (pinfunction "1_1") (pintype "unspecified"))
      (node (ref "U23") (pin "1") (pinfunction "1_1") (pintype "unspecified"))
    )
    (net (code "38") (name "Net-(D24-Pad1)") (class "Default")
      (node (ref "D24") (pin "1") (pinfunction "1_1") (pintype "unspecified"))
      (node (ref "U24") (pin "1") (pinfunction "1_1") (pintype "unspecified"))
    )
    (net (code "39") (name "Net-(D25-Pad1)") (class "Default")
      (node (ref "D25") (pin "1") (pinfunction "1_1") (pintype "unspecified"))
      (node (ref "U25") (pin "1") (pinfunction "1_1") (pintype "unspecified"))
    )
    (net (code "40") (name "Net-(D26-Pad1)") (class "Default")
      (node (ref "D26") (pin "1") (pinfunction "1_1") (pintype "unspecified"))
      (node (ref "U26") (pin "1") (pinfunction "1_1") (pintype "unspecified"))
    )
    (net (code "41") (name "Net-(D27-Pad1)") (class "Default")
      (node (ref "D27") (pin "1") (pinfunction "1_1") (pintype "unspecified"))
      (node (ref "U27") (pin "1") (pinfunction "1_1") (pintype "unspecified"))
    )
    (net (code "42") (name "Net-(D28-Pad1)") (class "Default")
      (node (ref "D28") (pin "1") (pinfunction "1_1") (pintype "unspecified"))
      (node (ref "U28") (pin "1") (pinfunction "1_1") (pintype "unspecified"))
    )
    (net (code "43") (name "Net-(D29-Pad1)") (class "Default")
      (node (ref "D29") (pin "1") (pinfunction "1_1") (pintype "unspecified"))
      (node (ref "U29") (pin "1") (pinfunction "1_1") (pintype "unspecified"))
    )
    (net (code "44") (name "Net-(D30-Pad1)") (class "Default")
      (node (ref "D30") (pin "1") (pinfunction "1_1") (pintype "unspecified"))
      (node (ref "U30") (pin "1") (pinfunction "1_1") (pintype "unspecified"))
    )
    (net (code "45") (name "Net-(D31-Pad1)") (class "Default")
      (node (ref "D31") (pin "1") (pinfunction "1_1") (pintype "unspecified"))
      (node (ref "U31") (pin "1") (pinfunction "1_1") (pintype "unspecified"))
    )
    (net (code "46") (name "Net-(D32-Pad1)") (class "Default")
      (node (ref "D32") (pin "1") (pinfunction "1_1") (pintype "unspecified"))
      (node (ref "U32") (pin "1") (pinfunction "1_1") (pintype "unspecified"))
    )
    (net (code "47") (name "Net-(D33-Pad1)") (class "Default")
      (node (ref "D33") (pin "1") (pinfunction "1_1") (pintype "unspecified"))
      (node (ref "U33") (pin "1") (pinfunction "1_1") (pintype "unspecified"))
    )
    (net (code "48") (name "Net-(D34-Pad1)") (class "Default")
      (node (ref "D34") (pin "1") (pinfunction "1_1") (pintype "unspecified"))
      (node (ref "U34") (pin "1") (pinfunction "1_1") (pintype "unspecified"))
    )
    (net (code "49") (name "Net-(D35-Pad1)") (class "Default")
      (node (ref "D35") (pin "1") (pinfunction "1_1") (pintype "unspecified"))
      (node (ref "U35") (pin "1") (pinfunction "1_1") (pintype "unspecified"))
    )
    (net (code "50") (name "Net-(D36-Pad1)") (class "Default")
      (node (ref "D36") (pin "1") (pinfunction "1_1") (pintype "unspecified"))
      (node (ref "U36") (pin "1") (pinfunction "1_1") (pintype "unspecified"))
    )
    (net (code "51") (name "Net-(D37-Pad1)") (class "Default")
      (node (ref "D37") (pin "1") (pinfunction "1_1") (pintype "unspecified"))
      (node (ref "U37") (pin "1") (pinfunction "1_1") (pintype "unspecified"))
    )
    (net (code "52") (name "Net-(D38-Pad1)") (class "Default")
      (node (ref "D38") (pin "1") (pinfunction "1_1") (pintype "unspecified"))
      (node (ref "U38") (pin "1") (pinfunction "1_1") (pintype "unspecified"))
    )
    (net (code "53") (name "Net-(D39-Pad1)") (class "Default")
      (node (ref "D39") (pin "1") (pinfunction "1_1") (pintype "unspecified"))
      (node (ref "U39") (pin "1") (pinfunction "1_1") (pintype "unspecified"))
    )
    (net (code "54") (name "Net-(D40-Pad1)") (class "Default")
      (node (ref "D40") (pin "1") (pinfunction "1_1") (pintype "unspecified"))
      (node (ref "U40") (pin "1") (pinfunction "1_1") (pintype "unspecified"))
    )
    (net (code "55") (name "Net-(D41-Pad1)") (class "Default")
      (node (ref "D41") (pin "1") (pinfunction "1_1") (pintype "unspecified"))
      (node (ref "U41") (pin "1") (pinfunction "1_1") (pintype "unspecified"))
    )
    (net (code "56") (name "Net-(D42-Pad1)") (class "Default")
      (node (ref "D42") (pin "1") (pinfunction "1_1") (pintype "unspecified"))
      (node (ref "U42") (pin "1") (pinfunction "1_1") (pintype "unspecified"))
    )
    (net (code "57") (name "Net-(D43-Pad1)") (class "Default")
      (node (ref "D43") (pin "1") (pinfunction "1_1") (pintype "unspecified"))
      (node (ref "U43") (pin "1") (pinfunction "1_1") (pintype "unspecified"))
    )
    (net (code "58") (name "Net-(D44-Pad1)") (class "Default")
      (node (ref "D44") (pin "1") (pinfunction "1_1") (pintype "unspecified"))
      (node (ref "U44") (pin "1") (pinfunction "1_1") (pintype "unspecified"))
    )
    (net (code "59") (name "Net-(D45-Pad1)") (class "Default")
      (node (ref "D45") (pin "1") (pinfunction "1_1") (pintype "unspecified"))
      (node (ref "U45") (pin "1") (pinfunction "1_1") (pintype "unspecified"))
    )
    (net (code "60") (name "Net-(D46-Pad1)") (class "Default")
      (node (ref "D46") (pin "1") (pinfunction "1_1") (pintype "unspecified"))
      (node (ref "U46") (pin "1") (pinfunction "1_1") (pintype "unspecified"))
    )
    (net (code "61") (name "Net-(D47-Pad1)") (class "Default")
      (node (ref "D47") (pin "1") (pinfunction "1_1") (pintype "unspecified"))
      (node (ref "U47") (pin "1") (pinfunction "1_1") (pintype "unspecified"))
    )
    (net (code "62") (name "Net-(U12-Pad1)") (class "Default")
      (node (ref "U12") (pin "1") (pinfunction "1_1") (pintype "unspecified"))
      (node (ref "U50") (pin "1") (pinfunction "1_1") (pintype "unspecified"))
    )
    (net (code "63") (name "RDY") (class "Default")
      (node (ref "U1") (pin "1") (pinfunction "P0.02_1") (pintype "input"))
      (node (ref "U2") (pin "1") (pinfunction "RDY_1") (pintype "unspecified"))
    )
    (net (code "64") (name "RESET") (class "Default")
      (node (ref "R4") (pin "1") (pinfunction "1_1") (pintype "unspecified"))
      (node (ref "U51") (pin "18") (pinfunction "RESET_18") (pintype "unspecified"))
    )
    (net (code "65") (name "ROW1") (class "Default")
      (node (ref "D1") (pin "2") (pinfunction "2_2") (pintype "unspecified"))
      (node (ref "D10") (pin "2") (pinfunction "2_2") (pintype "unspecified"))
      (node (ref "D11") (pin "2") (pinfunction "2_2") (pintype "unspecified"))
      (node (ref "D2") (pin "2") (pinfunction "2_2") (pintype "unspecified"))
      (node (ref "D3") (pin "2") (pinfunction "2_2") (pintype "unspecified"))
      (node (ref "D4") (pin "2") (pinfunction "2_2") (pintype "unspecified"))
      (node (ref "D5") (pin "2") (pinfunction "2_2") (pintype "unspecified"))
      (node (ref "D6") (pin "2") (pinfunction "2_2") (pintype "unspecified"))
      (node (ref "D7") (pin "2") (pinfunction "2_2") (pintype "unspecified"))
      (node (ref "D8") (pin "2") (pinfunction "2_2") (pintype "unspecified"))
      (node (ref "D9") (pin "2") (pinfunction "2_2") (pintype "unspecified"))
      (node (ref "U12") (pin "2") (pinfunction "2_2") (pintype "unspecified"))
      (node (ref "U51") (pin "21") (pinfunction "GPA0_21") (pintype "unspecified"))
    )
    (net (code "66") (name "ROW2") (class "Default")
      (node (ref "D13") (pin "2") (pinfunction "2_2") (pintype "unspecified"))
      (node (ref "D14") (pin "2") (pinfunction "2_2") (pintype "unspecified"))
      (node (ref "D15") (pin "2") (pinfunction "2_2") (pintype "unspecified"))
      (node (ref "D16") (pin "2") (pinfunction "2_2") (pintype "unspecified"))
      (node (ref "D17") (pin "2") (pinfunction "2_2") (pintype "unspecified"))
      (node (ref "D18") (pin "2") (pinfunction "2_2") (pintype "unspecified"))
      (node (ref "D19") (pin "2") (pinfunction "2_2") (pintype "unspecified"))
      (node (ref "D20") (pin "2") (pinfunction "2_2") (pintype "unspecified"))
      (node (ref "D21") (pin "2") (pinfunction "2_2") (pintype "unspecified"))
      (node (ref "D22") (pin "2") (pinfunction "2_2") (pintype "unspecified"))
      (node (ref "D23") (pin "2") (pinfunction "2_2") (pintype "unspecified"))
      (node (ref "D24") (pin "2") (pinfunction "2_2") (pintype "unspecified"))
      (node (ref "U51") (pin "22") (pinfunction "GPA1_22") (pintype "unspecified"))
    )
    (net (code "67") (name "ROW3") (class "Default")
      (node (ref "D25") (pin "2") (pinfunction "2_2") (pintype "unspecified"))
      (node (ref "D26") (pin "2") (pinfunction "2_2") (pintype "unspecified"))
      (node (ref "D27") (pin "2") (pinfunction "2_2") (pintype "unspecified"))
      (node (ref "D28") (pin "2") (pinfunction "2_2") (pintype "unspecified"))
      (node (ref "D29") (pin "2") (pinfunction "2_2") (pintype "unspecified"))
      (node (ref "D30") (pin "2") (pinfunction "2_2") (pintype "unspecified"))
      (node (ref "D31") (pin "2") (pinfunction "2_2") (pintype "unspecified"))
      (node (ref "D32") (pin "2") (pinfunction "2_2") (pintype "unspecified"))
      (node (ref "D33") (pin "2") (pinfunction "2_2") (pintype "unspecified"))
      (node (ref "D34") (pin "2") (pinfunction "2_2") (pintype "unspecified"))
      (node (ref "D35") (pin "2") (pinfunction "2_2") (pintype "unspecified"))
      (node (ref "D36") (pin "2") (pinfunction "2_2") (pintype "unspecified"))
      (node (ref "U51") (pin "23") (pinfunction "GPA2_23") (pintype "unspecified"))
    )
    (net (code "68") (name "ROW4") (class "Default")
      (node (ref "D37") (pin "2") (pinfunction "2_2") (pintype "unspecified"))
      (node (ref "D38") (pin "2") (pinfunction "2_2") (pintype "unspecified"))
      (node (ref "D39") (pin "2") (pinfunction "2_2") (pintype "unspecified"))
      (node (ref "D40") (pin "2") (pinfunction "2_2") (pintype "unspecified"))
      (node (ref "D41") (pin "2") (pinfunction "2_2") (pintype "unspecified"))
      (node (ref "D42") (pin "2") (pinfunction "2_2") (pintype "unspecified"))
      (node (ref "D43") (pin "2") (pinfunction "2_2") (pintype "unspecified"))
      (node (ref "D44") (pin "2") (pinfunction "2_2") (pintype "unspecified"))
      (node (ref "D45") (pin "2") (pinfunction "2_2") (pintype "unspecified"))
      (node (ref "D46") (pin "2") (pinfunction "2_2") (pintype "unspecified"))
      (node (ref "D47") (pin "2") (pinfunction "2_2") (pintype "unspecified"))
      (node (ref "U51") (pin "24") (pinfunction "GPA3_24") (pintype "unspecified"))
    )
    (net (code "69") (name "SCL") (class "Default")
      (node (ref "R2") (pin "1") (pinfunction "1_1") (pintype "unspecified"))
      (node (ref "U1") (pin "6") (pinfunction "P0.05_SCL_6") (pintype "unspecified"))
      (node (ref "U2") (pin "5") (pinfunction "SCL_5") (pintype "unspecified"))
      (node (ref "U51") (pin "12") (pinfunction "SCK_12") (pintype "unspecified"))
    )
    (net (code "70") (name "SDA") (class "Default")
      (node (ref "R1") (pin "1") (pinfunction "1_1") (pintype "unspecified"))
      (node (ref "U1") (pin "5") (pinfunction "P0.04_SDA_5") (pintype "unspecified"))
      (node (ref "U2") (pin "6") (pinfunction "SDA_6") (pintype "unspecified"))
      (node (ref "U51") (pin "13") (pinfunction "SDA_13") (pintype "unspecified"))
    )
    (net (code "71") (name "unconnected-(U1-5V-Pad14)") (class "Default")
      (node (ref "U1") (pin "14") (pinfunction "5V_14") (pintype "unspecified+no_connect"))
    )
    (net (code "72") (name "unconnected-(U1-P0.28-Pad3)") (class "Default")
      (node (ref "U1") (pin "3") (pinfunction "P0.28_3") (pintype "bidirectional+no_connect"))
    )
    (net (code "73") (name "unconnected-(U1-P0.29-Pad4)") (class "Default")
      (node (ref "U1") (pin "4") (pinfunction "P0.29_4") (pintype "unspecified+no_connect"))
    )
    (net (code "74") (name "unconnected-(U1-P1.11_TX-Pad7)") (class "Default")
      (node (ref "U1") (pin "7") (pinfunction "P1.11_TX_7") (pintype "unspecified+no_connect"))
    )
    (net (code "75") (name "unconnected-(U1-P1.12_RX-Pad8)") (class "Default")
      (node (ref "U1") (pin "8") (pinfunction "P1.12_RX_8") (pintype "unspecified+no_connect"))
    )
    (net (code "76") (name "unconnected-(U1-P1.13_SCK-Pad9)") (class "Default")
      (node (ref "U1") (pin "9") (pinfunction "P1.13_SCK_9") (pintype "unspecified+no_connect"))
    )
    (net (code "77") (name "unconnected-(U1-P1.14_MISO-Pad10)") (class "Default")
      (node (ref "U1") (pin "10") (pinfunction "P1.14_MISO_10") (pintype "unspecified+no_connect"))
    )
    (net (code "78") (name "unconnected-(U1-P1.15_MOSI-Pad11)") (class "Default")
      (node (ref "U1") (pin "11") (pinfunction "P1.15_MOSI_11") (pintype "unspecified+no_connect"))
    )
    (net (code "79") (name "unconnected-(U1-RST-Pad17)") (class "Default")
      (node (ref "U1") (pin "17") (pinfunction "RST_17") (pintype "unspecified+no_connect"))
    )
    (net (code "80") (name "unconnected-(U1-SWCLK-Pad16)") (class "Default")
      (node (ref "U1") (pin "16") (pinfunction "SWCLK_16") (pintype "unspecified+no_connect"))
    )
    (net (code "81") (name "unconnected-(U1-SWDIO-Pad15)") (class "Default")
      (node (ref "U1") (pin "15") (pinfunction "SWDIO_15") (pintype "unspecified+no_connect"))
    )
    (net (code "82") (name "unconnected-(U3-Pad3)") (class "Default")
      (node (ref "U3") (pin "3") (pinfunction "3_3") (pintype "unspecified"))
    )
    (net (code "83") (name "unconnected-(U4-Pad3)") (class "Default")
      (node (ref "U4") (pin "3") (pinfunction "3_3") (pintype "unspecified"))
    )
    (net (code "84") (name "unconnected-(U5-Pad3)") (class "Default")
      (node (ref "U5") (pin "3") (pinfunction "3_3") (pintype "unspecified"))
    )
    (net (code "85") (name "unconnected-(U6-Pad3)") (class "Default")
      (node (ref "U6") (pin "3") (pinfunction "3_3") (pintype "unspecified"))
    )
    (net (code "86") (name "unconnected-(U7-Pad3)") (class "Default")
      (node (ref "U7") (pin "3") (pinfunction "3_3") (pintype "unspecified"))
    )
    (net (code "87") (name "unconnected-(U8-Pad3)") (class "Default")
      (node (ref "U8") (pin "3") (pinfunction "3_3") (pintype "unspecified"))
    )
    (net (code "88") (name "unconnected-(U9-Pad3)") (class "Default")
      (node (ref "U9") (pin "3") (pinfunction "3_3") (pintype "unspecified"))
    )
    (net (code "89") (name "unconnected-(U10-Pad3)") (class "Default")
      (node (ref "U10") (pin "3") (pinfunction "3_3") (pintype "unspecified"))
    )
    (net (code "90") (name "unconnected-(U11-Pad3)") (class "Default")
      (node (ref "U11") (pin "3") (pinfunction "3_3") (pintype "unspecified"))
    )
    (net (code "91") (name "unconnected-(U13-Pad3)") (class "Default")
      (node (ref "U13") (pin "3") (pinfunction "3_3") (pintype "unspecified"))
    )
    (net (code "92") (name "unconnected-(U14-Pad3)") (class "Default")
      (node (ref "U14") (pin "3") (pinfunction "3_3") (pintype "unspecified"))
    )
    (net (code "93") (name "unconnected-(U15-Pad3)") (class "Default")
      (node (ref "U15") (pin "3") (pinfunction "3_3") (pintype "unspecified"))
    )
    (net (code "94") (name "unconnected-(U16-Pad3)") (class "Default")
      (node (ref "U16") (pin "3") (pinfunction "3_3") (pintype "unspecified"))
    )
    (net (code "95") (name "unconnected-(U17-Pad3)") (class "Default")
      (node (ref "U17") (pin "3") (pinfunction "3_3") (pintype "unspecified"))
    )
    (net (code "96") (name "unconnected-(U18-Pad3)") (class "Default")
      (node (ref "U18") (pin "3") (pinfunction "3_3") (pintype "unspecified"))
    )
    (net (code "97") (name "unconnected-(U19-Pad3)") (class "Default")
      (node (ref "U19") (pin "3") (pinfunction "3_3") (pintype "unspecified"))
    )
    (net (code "98") (name "unconnected-(U20-Pad3)") (class "Default")
      (node (ref "U20") (pin "3") (pinfunction "3_3") (pintype "unspecified"))
    )
    (net (code "99") (name "unconnected-(U21-Pad3)") (class "Default")
      (node (ref "U21") (pin "3") (pinfunction "3_3") (pintype "unspecified"))
    )
    (net (code "100") (name "unconnected-(U22-Pad3)") (class "Default")
      (node (ref "U22") (pin "3") (pinfunction "3_3") (pintype "unspecified"))
    )
    (net (code "101") (name "unconnected-(U23-Pad3)") (class "Default")
      (node (ref "U23") (pin "3") (pinfunction "3_3") (pintype "unspecified"))
    )
    (net (code "102") (name "unconnected-(U24-Pad3)") (class "Default")
      (node (ref "U24") (pin "3") (pinfunction "3_3") (pintype "unspecified"))
    )
    (net (code "103") (name "unconnected-(U25-Pad3)") (class "Default")
      (node (ref "U25") (pin "3") (pinfunction "3_3") (pintype "unspecified"))
    )
    (net (code "104") (name "unconnected-(U26-Pad3)") (class "Default")
      (node (ref "U26") (pin "3") (pinfunction "3_3") (pintype "unspecified"))
    )
    (net (code "105") (name "unconnected-(U27-Pad3)") (class "Default")
      (node (ref "U27") (pin "3") (pinfunction "3_3") (pintype "unspecified"))
    )
    (net (code "106") (name "unconnected-(U28-Pad3)") (class "Default")
      (node (ref "U28") (pin "3") (pinfunction "3_3") (pintype "unspecified"))
    )
    (net (code "107") (name "unconnected-(U29-Pad3)") (class "Default")
      (node (ref "U29") (pin "3") (pinfunction "3_3") (pintype "unspecified"))
    )
    (net (code "108") (name "unconnected-(U30-Pad3)") (class "Default")
      (node (ref "U30") (pin "3") (pinfunction "3_3") (pintype "unspecified"))
    )
    (net (code "109") (name "unconnected-(U31-Pad3)") (class "Default")
      (node (ref "U31") (pin "3") (pinfunction "3_3") (pintype "unspecified"))
    )
    (net (code "110") (name "unconnected-(U32-Pad3)") (class "Default")
      (node (ref "U32") (pin "3") (pinfunction "3_3") (pintype "unspecified"))
    )
    (net (code "111") (name "unconnected-(U33-Pad3)") (class "Default")
      (node (ref "U33") (pin "3") (pinfunction "3_3") (pintype "unspecified"))
    )
    (net (code "112") (name "unconnected-(U34-Pad3)") (class "Default")
      (node (ref "U34") (pin "3") (pinfunction "3_3") (pintype "unspecified"))
    )
    (net (code "113") (name "unconnected-(U35-Pad3)") (class "Default")
      (node (ref "U35") (pin "3") (pinfunction "3_3") (pintype "unspecified"))
    )
    (net (code "114") (name "unconnected-(U36-Pad3)") (class "Default")
      (node (ref "U36") (pin "3") (pinfunction "3_3") (pintype "unspecified"))
    )
    (net (code "115") (name "unconnected-(U37-Pad3)") (class "Default")
      (node (ref "U37") (pin "3") (pinfunction "3_3") (pintype "unspecified"))
    )
    (net (code "116") (name "unconnected-(U38-Pad3)") (class "Default")
      (node (ref "U38") (pin "3") (pinfunction "3_3") (pintype "unspecified"))
    )
    (net (code "117") (name "unconnected-(U39-Pad3)") (class "Default")
      (node (ref "U39") (pin "3") (pinfunction "3_3") (pintype "unspecified"))
    )
    (net (code "118") (name "unconnected-(U40-Pad3)") (class "Default")
      (node (ref "U40") (pin "3") (pinfunction "3_3") (pintype "unspecified"))
    )
    (net (code "119") (name "unconnected-(U41-Pad3)") (class "Default")
      (node (ref "U41") (pin "3") (pinfunction "3_3") (pintype "unspecified"))
    )
    (net (code "120") (name "unconnected-(U42-Pad3)") (class "Default")
      (node (ref "U42") (pin "3") (pinfunction "3_3") (pintype "unspecified"))
    )
    (net (code "121") (name "unconnected-(U43-Pad3)") (class "Default")
      (node (ref "U43") (pin "3") (pinfunction "3_3") (pintype "unspecified"))
    )
    (net (code "122") (name "unconnected-(U44-Pad3)") (class "Default")
      (node (ref "U44") (pin "3") (pinfunction "3_3") (pintype "unspecified"))
    )
    (net (code "123") (name "unconnected-(U45-Pad3)") (class "Default")
      (node (ref "U45") (pin "3") (pinfunction "3_3") (pintype "unspecified"))
    )
    (net (code "124") (name "unconnected-(U46-Pad3)") (class "Default")
      (node (ref "U46") (pin "3") (pinfunction "3_3") (pintype "unspecified"))
    )
    (net (code "125") (name "unconnected-(U47-Pad3)") (class "Default")
      (node (ref "U47") (pin "3") (pinfunction "3_3") (pintype "unspecified"))
    )
    (net (code "126") (name "unconnected-(U48-Pad3)") (class "Default")
      (node (ref "U48") (pin "3") (pinfunction "3_3") (pintype "unspecified"))
    )
    (net (code "127") (name "unconnected-(U49-Pad3)") (class "Default")
      (node (ref "U49") (pin "3") (pinfunction "3_3") (pintype "unspecified"))
    )
    (net (code "128") (name "unconnected-(U50-Pad3)") (class "Default")
      (node (ref "U50") (pin "3") (pinfunction "3_3") (pintype "unspecified"))
    )
    (net (code "129") (name "unconnected-(U51-INTA-Pad20)") (class "Default")
      (node (ref "U51") (pin "20") (pinfunction "INTA_20") (pintype "unspecified+no_connect"))
    )
    (net (code "130") (name "unconnected-(U51-INTB-Pad19)") (class "Default")
      (node (ref "U51") (pin "19") (pinfunction "INTB_19") (pintype "unspecified+no_connect"))
    )
    (net (code "131") (name "unconnected-(U51-NC-Pad11)") (class "Default")
      (node (ref "U51") (pin "11") (pinfunction "NC_11") (pintype "unspecified+no_connect"))
    )
    (net (code "132") (name "unconnected-(U51-NC-Pad14)") (class "Default")
      (node (ref "U51") (pin "14") (pinfunction "NC_14") (pintype "unspecified+no_connect"))
    )
  )
)
